# motor_control_cape.net
KiCad netlist of a schematic drawn in EAGLE
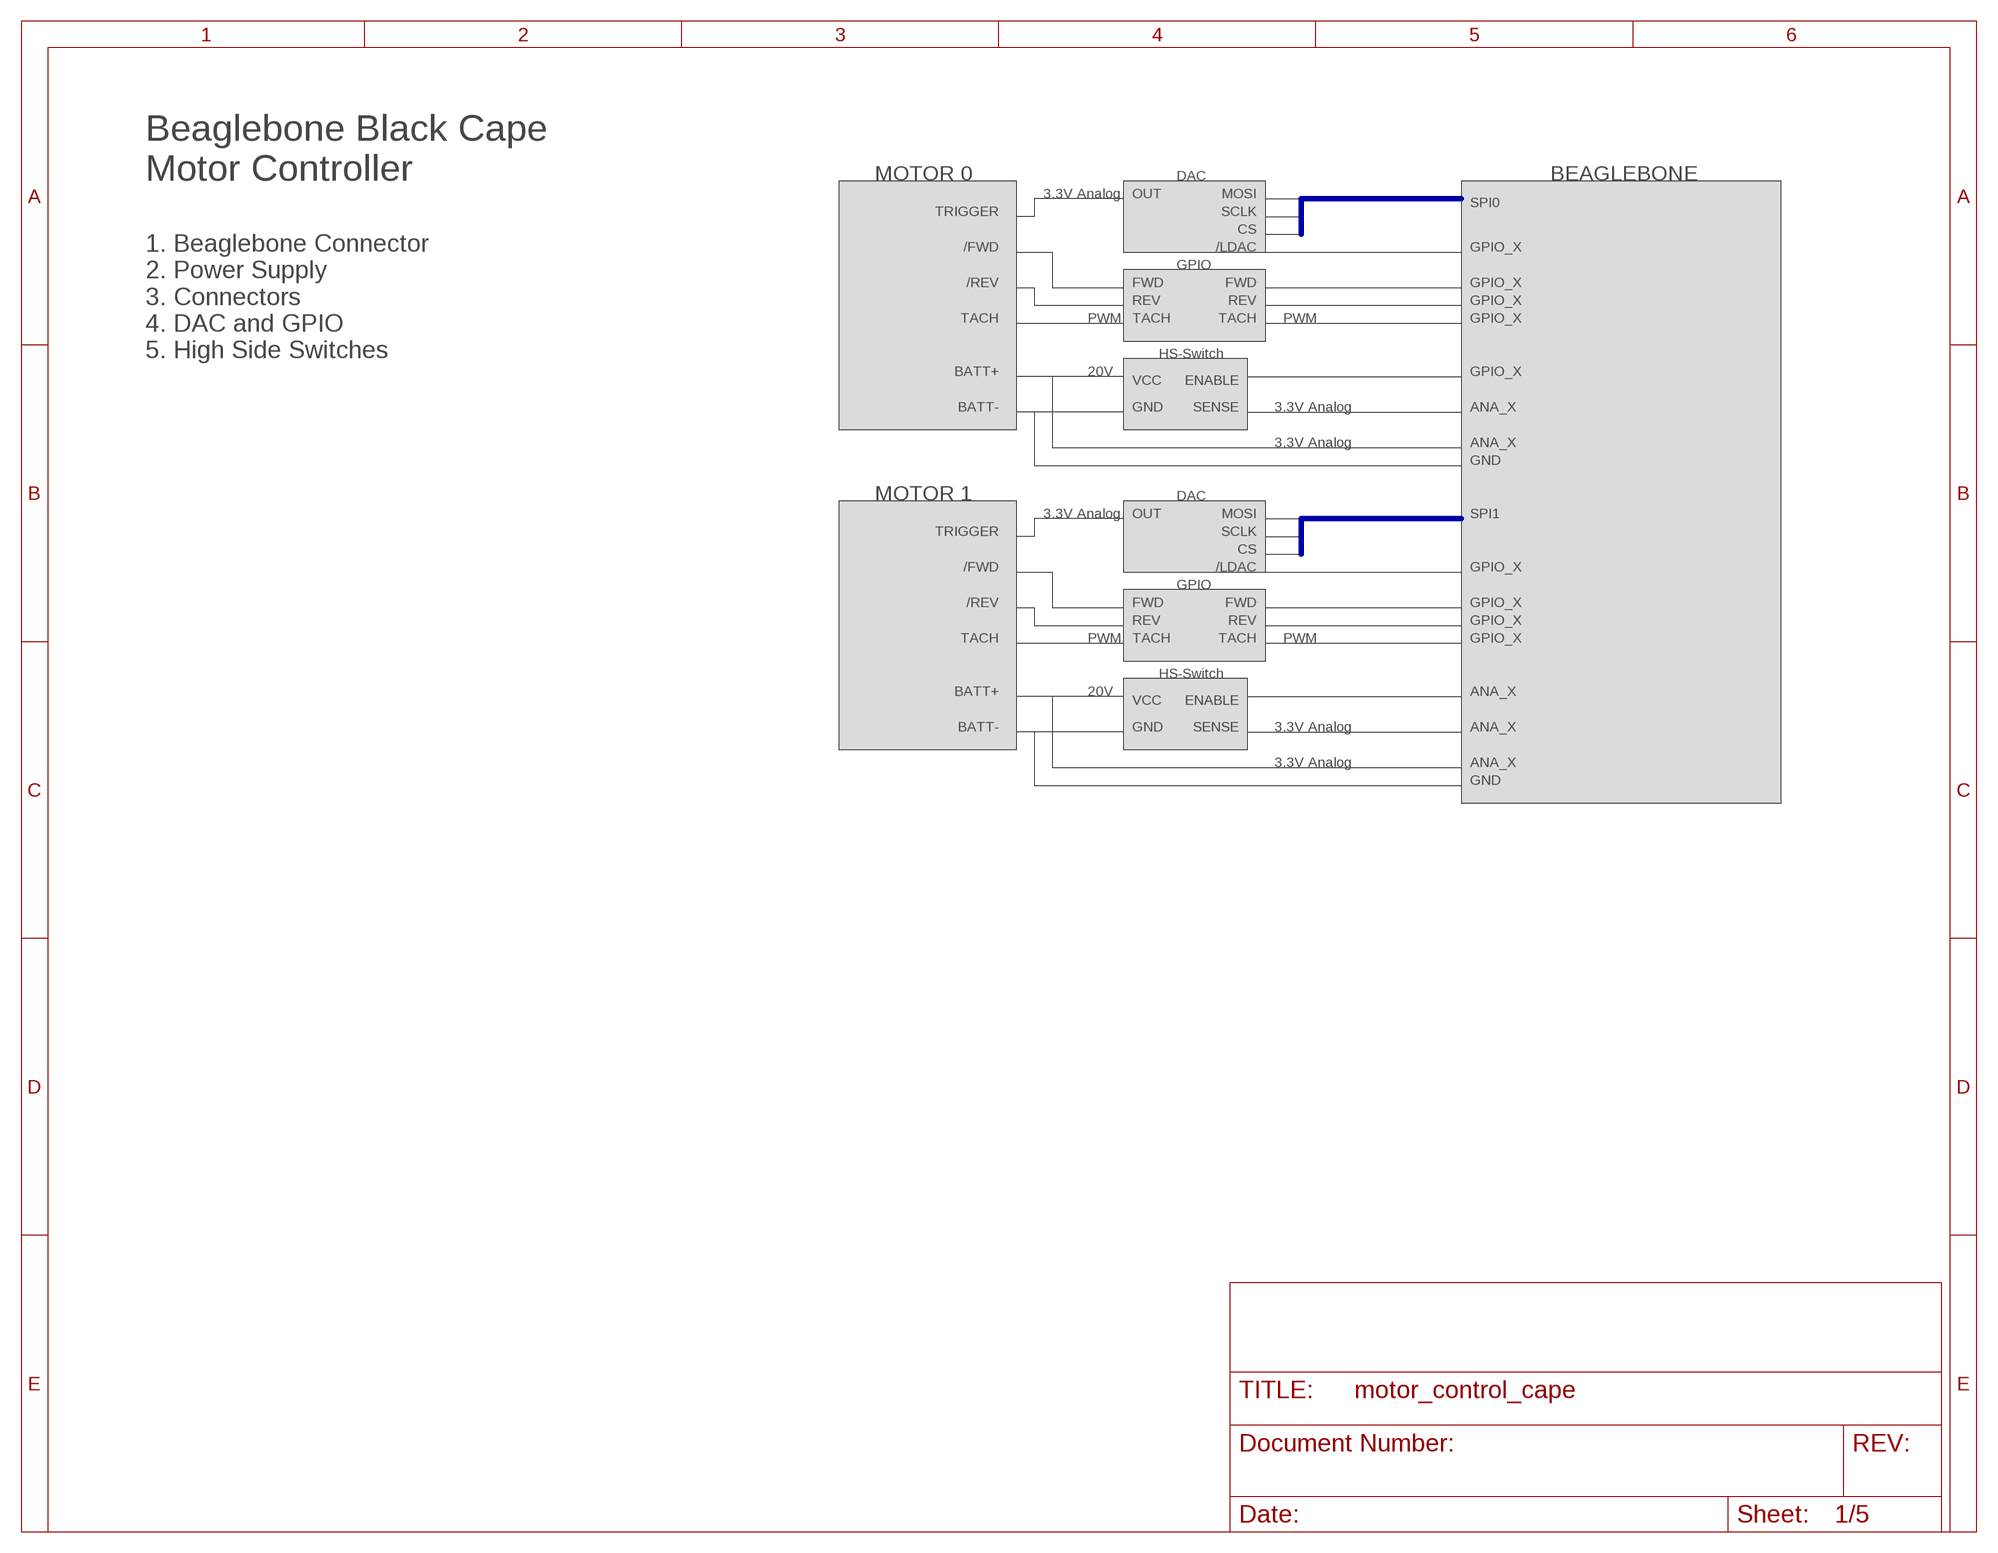
[diagram p0: schematic, sheet 1]
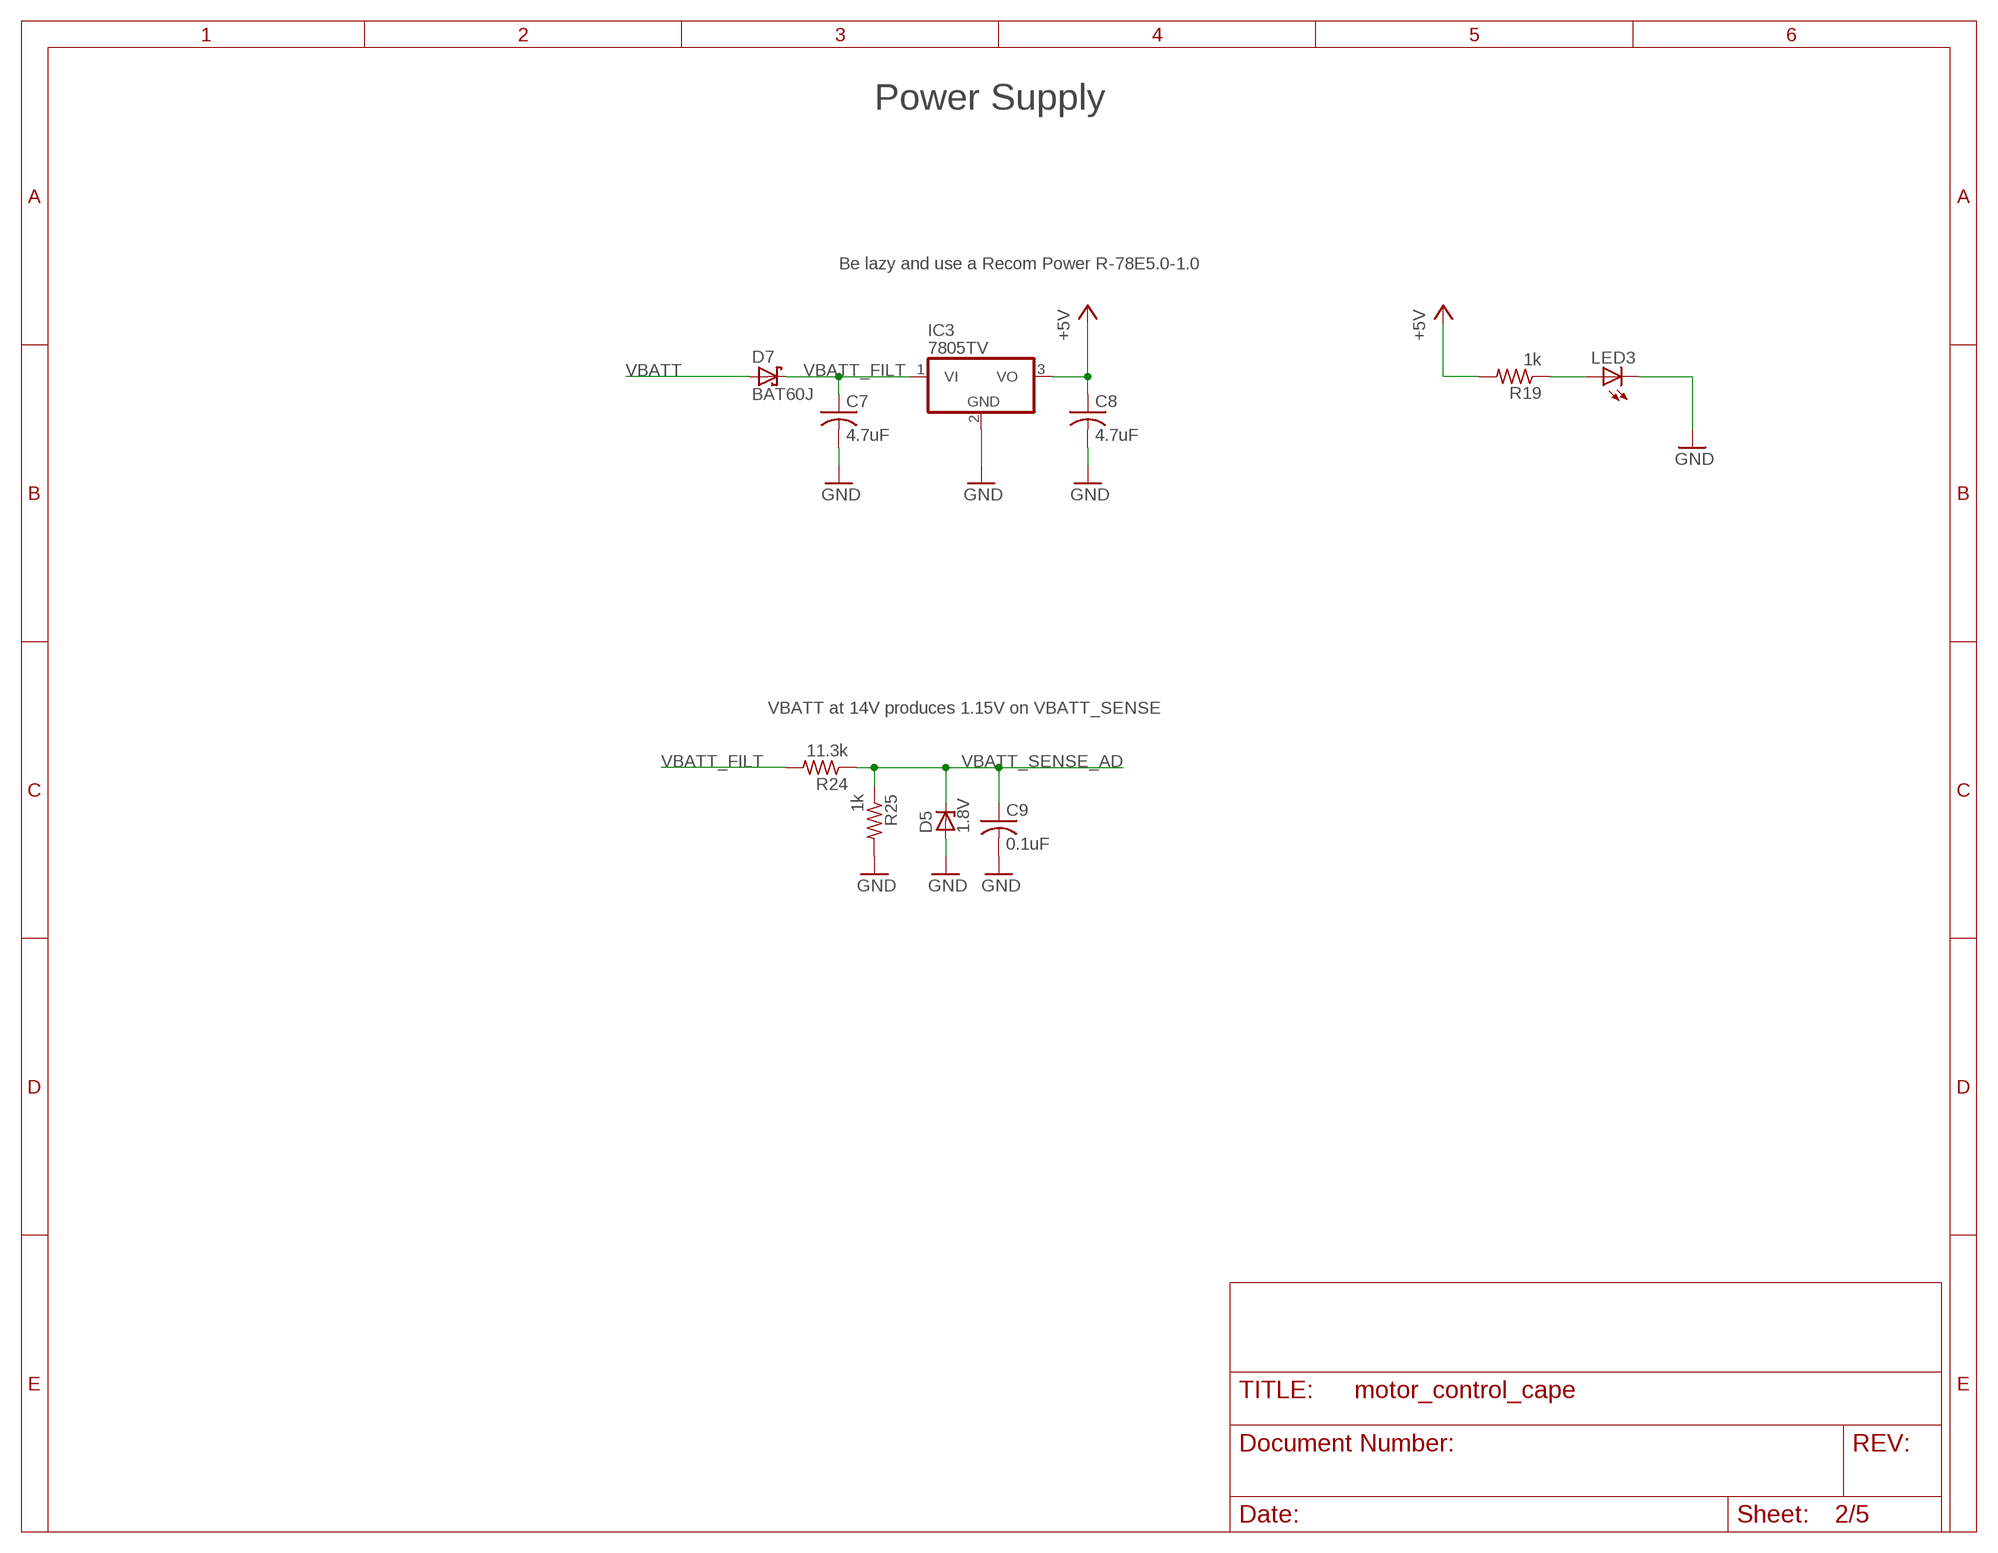
[diagram p1: schematic, sheet 2]
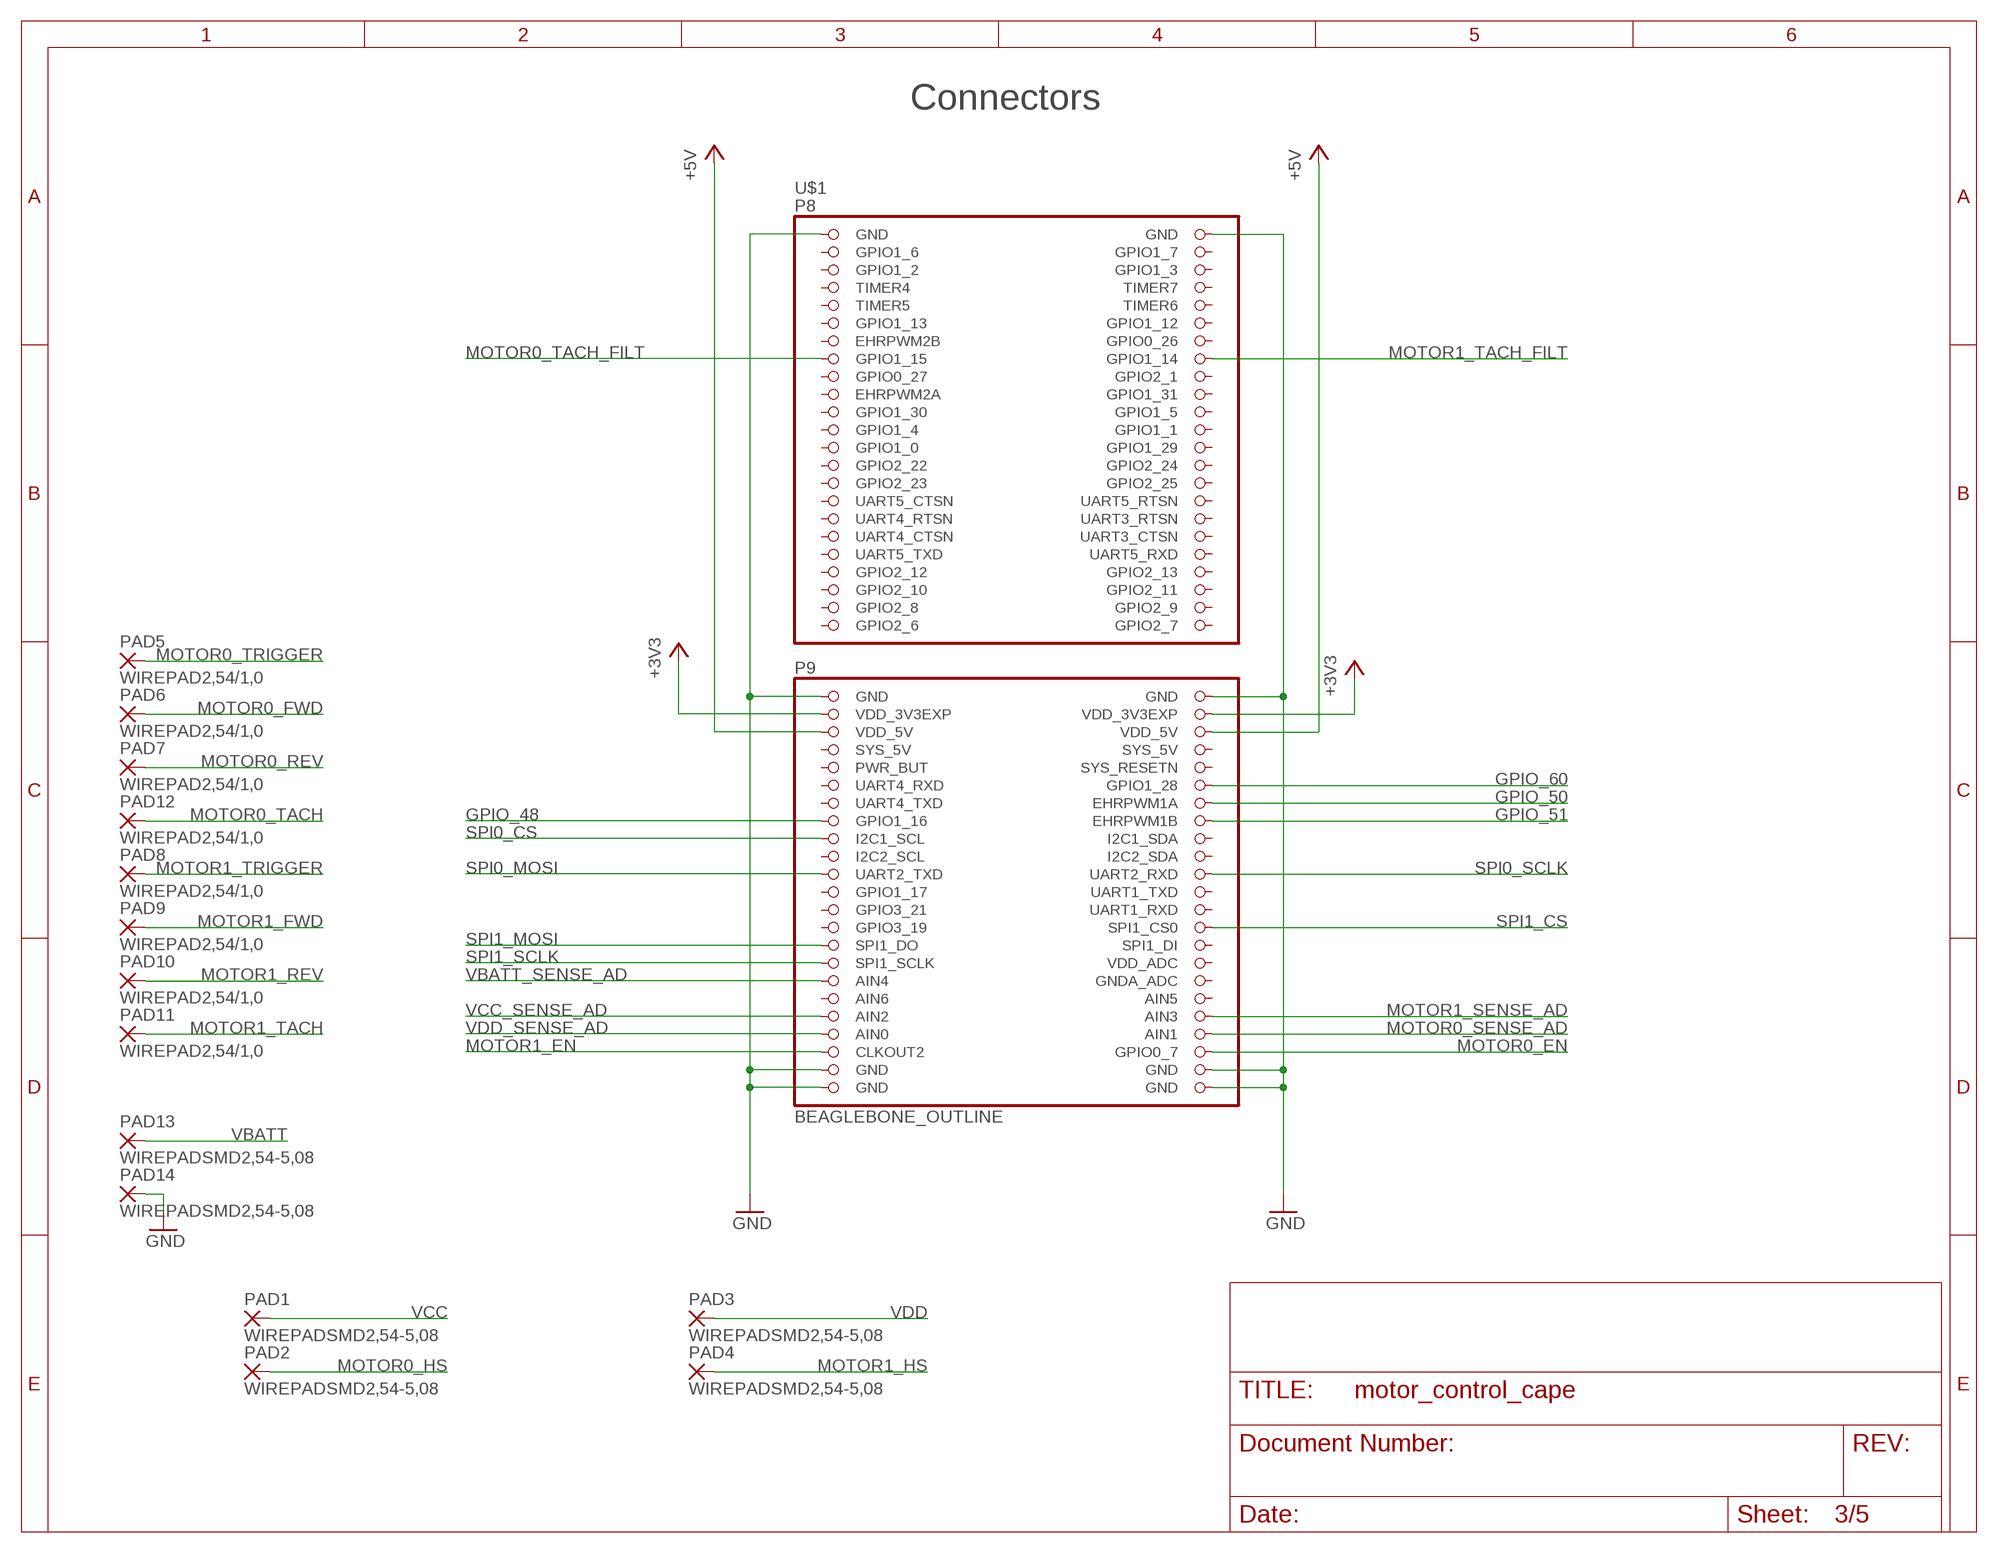
[diagram p2: schematic, sheet 3]
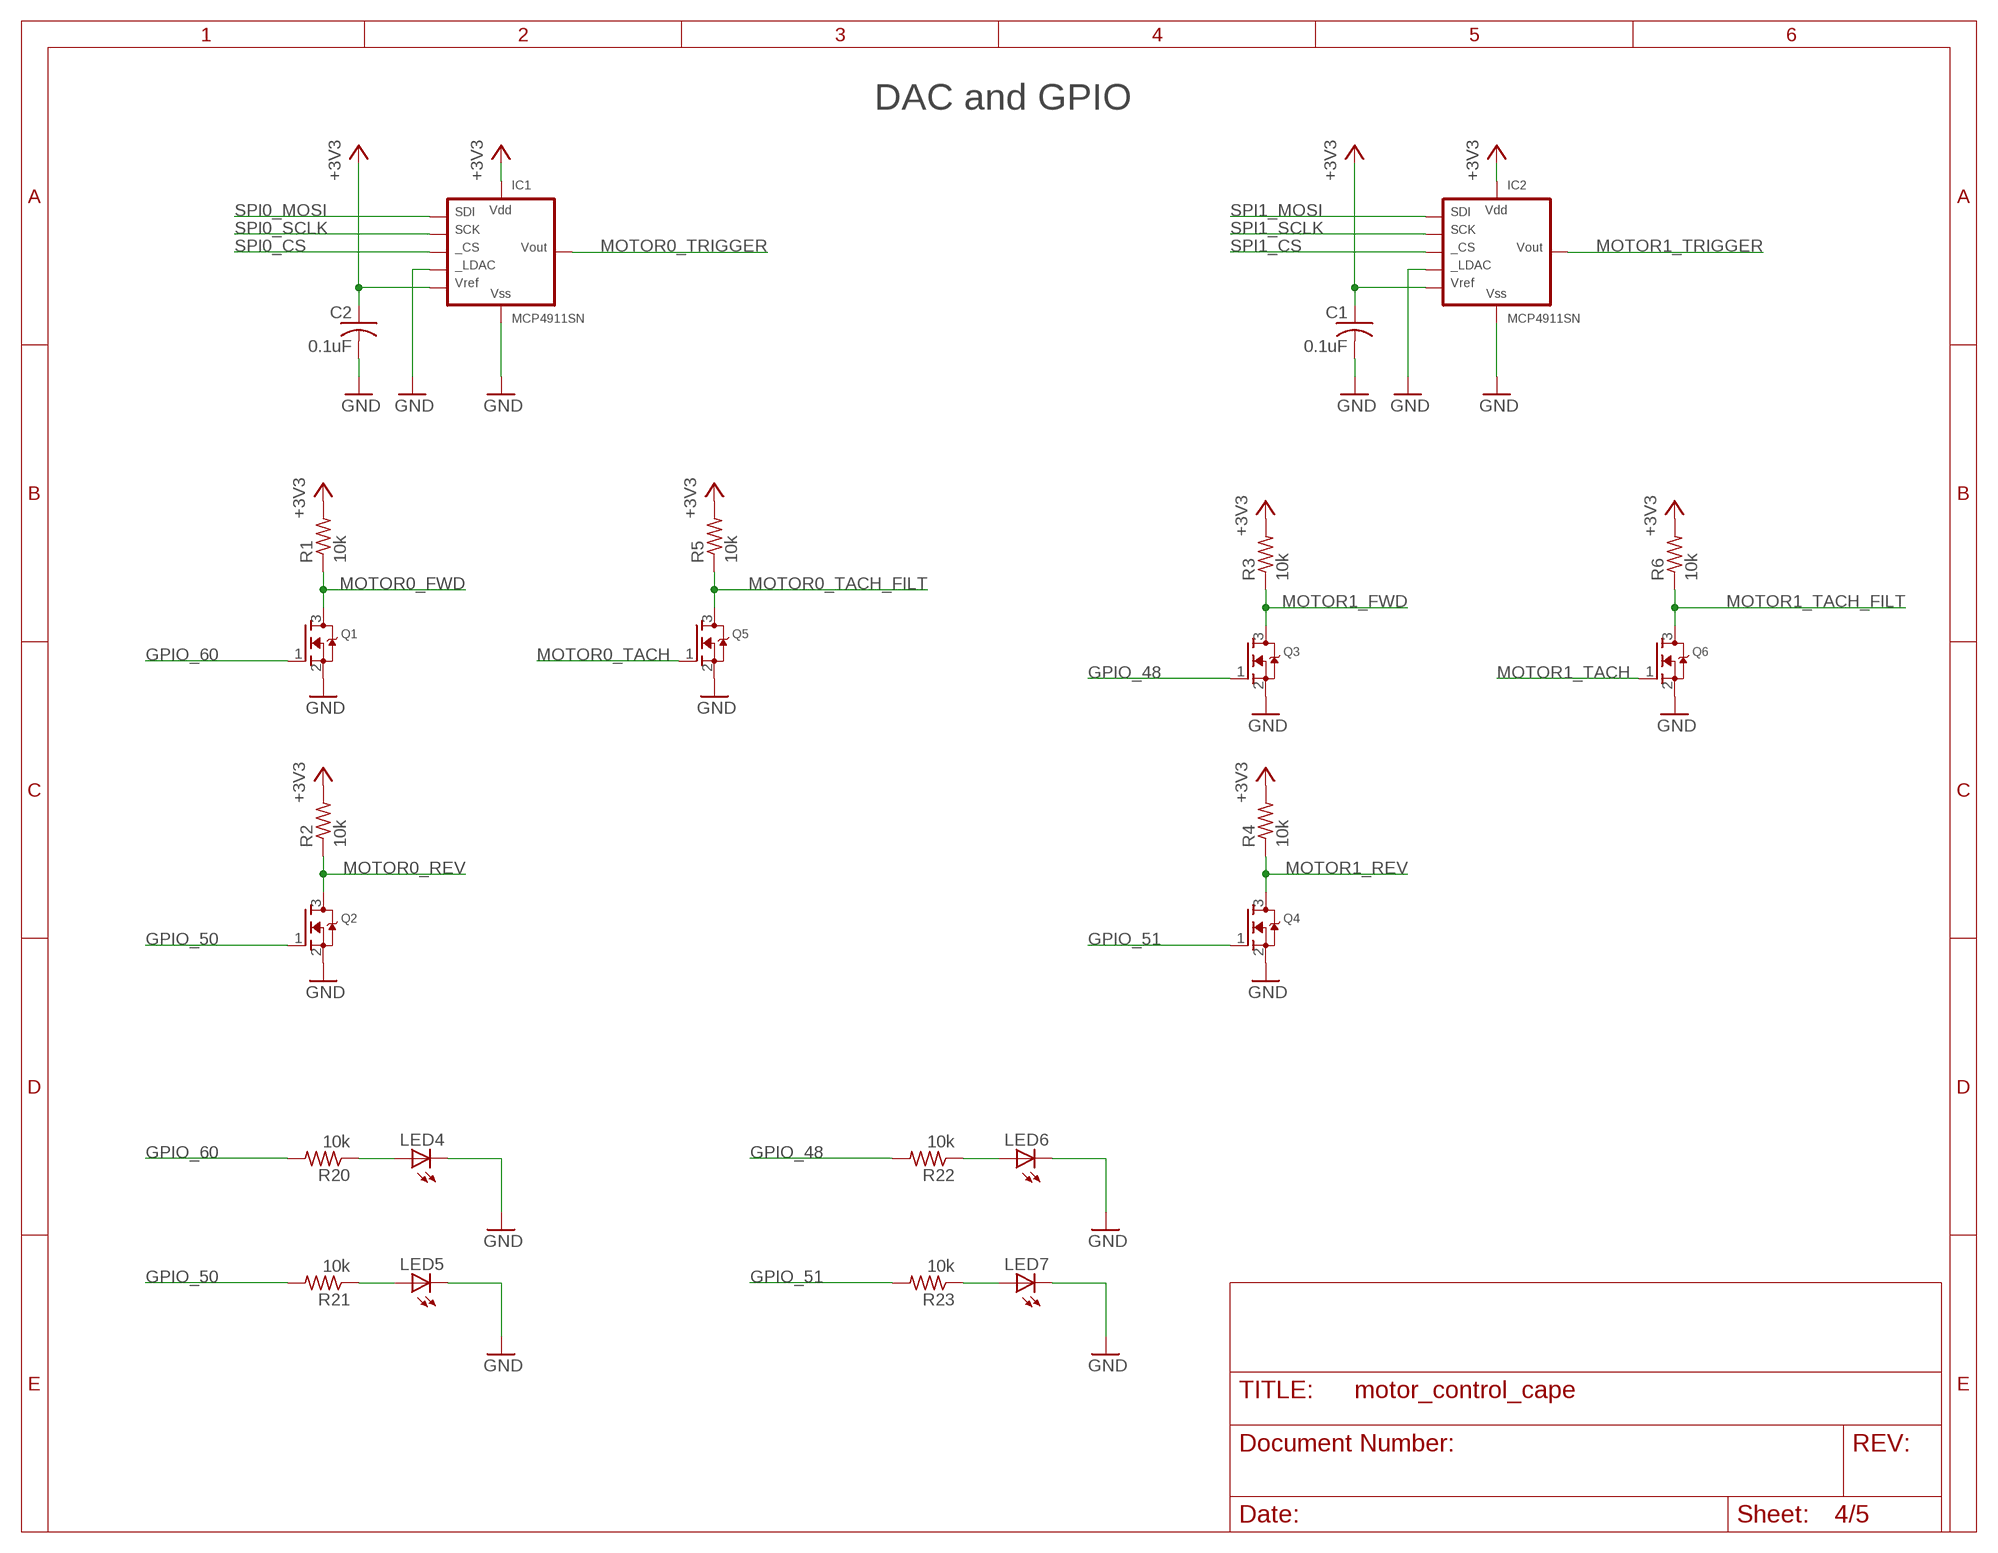
[diagram p3: schematic, sheet 4]
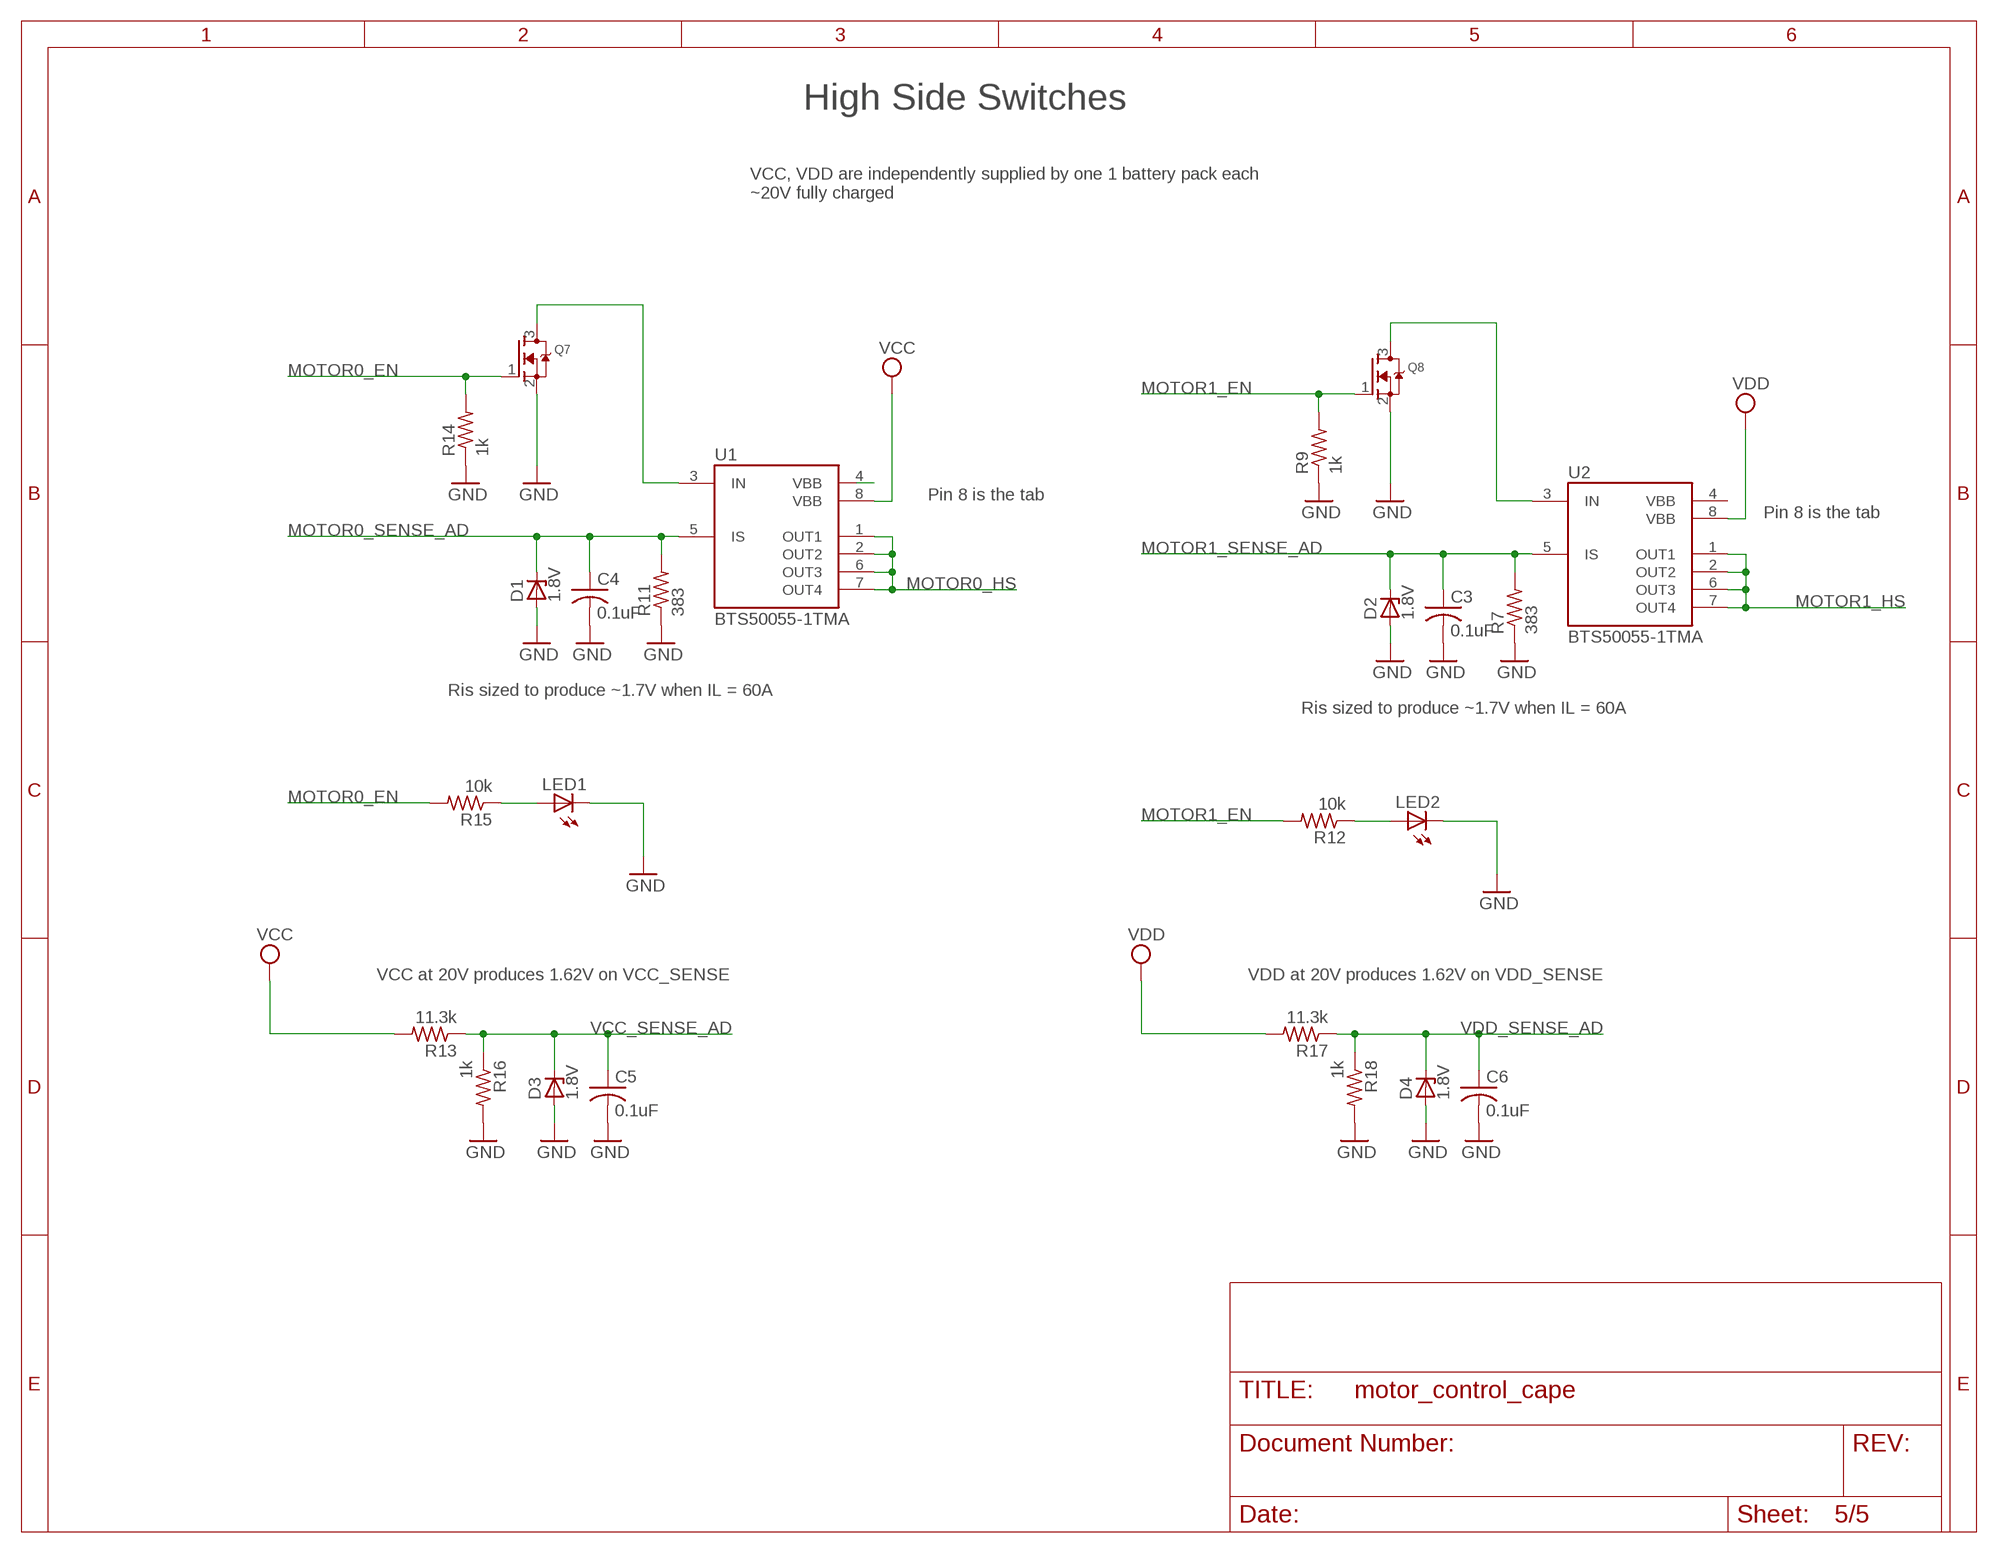
[diagram p4: schematic, sheet 5]

(export (version "E")
  (design (tool "Eeschema 10.0.6"))
  (components
    (comp (ref "C1")
      (value "0.1uF")
      (footprint "eagle-import:C0603")
      (libsource (lib "eagle-import") (part "C-USC0603"))
    )
    (comp (ref "C2")
      (value "0.1uF")
      (footprint "eagle-import:C0603")
      (libsource (lib "eagle-import") (part "C-USC0603"))
    )
    (comp (ref "IC1")
      (value "MCP4911SN")
      (footprint "eagle-import:SO-08")
      (libsource (lib "eagle-import") (part "MCP4911SN"))
    )
    (comp (ref "IC2")
      (value "MCP4911SN")
      (footprint "eagle-import:SO-08")
      (libsource (lib "eagle-import") (part "MCP4911SN"))
    )
    (comp (ref "LED4")
      (value "LEDCHIPLED_0603")
      (footprint "eagle-import:CHIPLED_0603")
      (libsource (lib "eagle-import") (part "LEDCHIPLED_0603"))
    )
    (comp (ref "LED5")
      (value "LEDCHIPLED_0603")
      (footprint "eagle-import:CHIPLED_0603")
      (libsource (lib "eagle-import") (part "LEDCHIPLED_0603"))
    )
    (comp (ref "LED6")
      (value "LEDCHIPLED_0603")
      (footprint "eagle-import:CHIPLED_0603")
      (libsource (lib "eagle-import") (part "LEDCHIPLED_0603"))
    )
    (comp (ref "LED7")
      (value "LEDCHIPLED_0603")
      (footprint "eagle-import:CHIPLED_0603")
      (libsource (lib "eagle-import") (part "LEDCHIPLED_0603"))
    )
    (comp (ref "Q1")
      (value "MOSFET-NREFLOW")
      (footprint "eagle-import:SOT23")
      (libsource (lib "eagle-import") (part "MOSFET-NREFLOW"))
    )
    (comp (ref "Q2")
      (value "MOSFET-NREFLOW")
      (footprint "eagle-import:SOT23")
      (libsource (lib "eagle-import") (part "MOSFET-NREFLOW"))
    )
    (comp (ref "Q3")
      (value "MOSFET-NREFLOW")
      (footprint "eagle-import:SOT23")
      (libsource (lib "eagle-import") (part "MOSFET-NREFLOW"))
    )
    (comp (ref "Q4")
      (value "MOSFET-NREFLOW")
      (footprint "eagle-import:SOT23")
      (libsource (lib "eagle-import") (part "MOSFET-NREFLOW"))
    )
    (comp (ref "Q5")
      (value "MOSFET-NREFLOW")
      (footprint "eagle-import:SOT23")
      (libsource (lib "eagle-import") (part "MOSFET-NREFLOW"))
    )
    (comp (ref "Q6")
      (value "MOSFET-NREFLOW")
      (footprint "eagle-import:SOT23")
      (libsource (lib "eagle-import") (part "MOSFET-NREFLOW"))
    )
    (comp (ref "R1")
      (value "10k")
      (footprint "eagle-import:R0603")
      (libsource (lib "eagle-import") (part "resistor_R-US_R0603"))
    )
    (comp (ref "R2")
      (value "10k")
      (footprint "eagle-import:R0603")
      (libsource (lib "eagle-import") (part "resistor_R-US_R0603"))
    )
    (comp (ref "R3")
      (value "10k")
      (footprint "eagle-import:R0603")
      (libsource (lib "eagle-import") (part "resistor_R-US_R0603"))
    )
    (comp (ref "R4")
      (value "10k")
      (footprint "eagle-import:R0603")
      (libsource (lib "eagle-import") (part "resistor_R-US_R0603"))
    )
    (comp (ref "R5")
      (value "10k")
      (footprint "eagle-import:R0603")
      (libsource (lib "eagle-import") (part "resistor_R-US_R0603"))
    )
    (comp (ref "R6")
      (value "10k")
      (footprint "eagle-import:R0603")
      (libsource (lib "eagle-import") (part "resistor_R-US_R0603"))
    )
    (comp (ref "R20")
      (value "10k")
      (footprint "eagle-import:R0603")
      (libsource (lib "eagle-import") (part "R-US_R0603"))
    )
    (comp (ref "R21")
      (value "10k")
      (footprint "eagle-import:R0603")
      (libsource (lib "eagle-import") (part "R-US_R0603"))
    )
    (comp (ref "R22")
      (value "10k")
      (footprint "eagle-import:R0603")
      (libsource (lib "eagle-import") (part "R-US_R0603"))
    )
    (comp (ref "R23")
      (value "10k")
      (footprint "eagle-import:R0603")
      (libsource (lib "eagle-import") (part "R-US_R0603"))
    )
    (comp (ref "C3")
      (value "0.1uF")
      (footprint "eagle-import:C0603")
      (libsource (lib "eagle-import") (part "C-USC0603"))
    )
    (comp (ref "C4")
      (value "0.1uF")
      (footprint "eagle-import:C0603")
      (libsource (lib "eagle-import") (part "C-USC0603"))
    )
    (comp (ref "C5")
      (value "0.1uF")
      (footprint "eagle-import:C0603")
      (libsource (lib "eagle-import") (part "C-USC0603"))
    )
    (comp (ref "C6")
      (value "0.1uF")
      (footprint "eagle-import:C0603")
      (libsource (lib "eagle-import") (part "C-USC0603"))
    )
    (comp (ref "D1")
      (value "1.8V")
      (footprint "eagle-import:SOT23")
      (libsource (lib "eagle-import") (part "ZENER-DIODESOT23"))
    )
    (comp (ref "D2")
      (value "1.8V")
      (footprint "eagle-import:SOT23")
      (libsource (lib "eagle-import") (part "ZENER-DIODESOT23"))
    )
    (comp (ref "D3")
      (value "1.8V")
      (footprint "eagle-import:SOT23")
      (libsource (lib "eagle-import") (part "ZENER-DIODESOT23"))
    )
    (comp (ref "D4")
      (value "1.8V")
      (footprint "eagle-import:SOT23")
      (libsource (lib "eagle-import") (part "ZENER-DIODESOT23"))
    )
    (comp (ref "LED1")
      (value "LEDCHIPLED_0603")
      (footprint "eagle-import:CHIPLED_0603")
      (libsource (lib "eagle-import") (part "LEDCHIPLED_0603"))
    )
    (comp (ref "LED2")
      (value "LEDCHIPLED_0603")
      (footprint "eagle-import:CHIPLED_0603")
      (libsource (lib "eagle-import") (part "LEDCHIPLED_0603"))
    )
    (comp (ref "Q7")
      (value "MOSFET-NREFLOW")
      (footprint "eagle-import:SOT23")
      (libsource (lib "eagle-import") (part "MOSFET-NREFLOW"))
    )
    (comp (ref "Q8")
      (value "MOSFET-NREFLOW")
      (footprint "eagle-import:SOT23")
      (libsource (lib "eagle-import") (part "MOSFET-NREFLOW"))
    )
    (comp (ref "R7")
      (value "383")
      (footprint "eagle-import:R0603")
      (libsource (lib "eagle-import") (part "R-US_R0603"))
    )
    (comp (ref "R9")
      (value "1k")
      (footprint "eagle-import:R0603")
      (libsource (lib "eagle-import") (part "R-US_R0603"))
    )
    (comp (ref "R11")
      (value "383")
      (footprint "eagle-import:R0603")
      (libsource (lib "eagle-import") (part "R-US_R0603"))
    )
    (comp (ref "R12")
      (value "10k")
      (footprint "eagle-import:R0603")
      (libsource (lib "eagle-import") (part "R-US_R0603"))
    )
    (comp (ref "R13")
      (value "11.3k")
      (footprint "eagle-import:R0603")
      (libsource (lib "eagle-import") (part "R-US_R0603"))
    )
    (comp (ref "R14")
      (value "1k")
      (footprint "eagle-import:R0603")
      (libsource (lib "eagle-import") (part "R-US_R0603"))
    )
    (comp (ref "R15")
      (value "10k")
      (footprint "eagle-import:R0603")
      (libsource (lib "eagle-import") (part "R-US_R0603"))
    )
    (comp (ref "R16")
      (value "1k")
      (footprint "eagle-import:R0603")
      (libsource (lib "eagle-import") (part "R-US_R0603"))
    )
    (comp (ref "R17")
      (value "11.3k")
      (footprint "eagle-import:R0603")
      (libsource (lib "eagle-import") (part "R-US_R0603"))
    )
    (comp (ref "R18")
      (value "1k")
      (footprint "eagle-import:R0603")
      (libsource (lib "eagle-import") (part "R-US_R0603"))
    )
    (comp (ref "U1")
      (value "BTS50055-1TMA")
      (footprint "eagle-import:TO127P1385X450-8N-V")
      (libsource (lib "eagle-import") (part "BTS50055-1TMA"))
    )
    (comp (ref "U2")
      (value "BTS50055-1TMA")
      (footprint "eagle-import:TO127P1385X450-8N-V")
      (libsource (lib "eagle-import") (part "BTS50055-1TMA"))
    )
    (comp (ref "PAD1")
      (value "WIREPADSMD2,54-5,08")
      (footprint "eagle-import:SMD2,54-5,08")
      (libsource (lib "eagle-import") (part "WIREPADSMD2,54-5,08"))
    )
    (comp (ref "PAD2")
      (value "WIREPADSMD2,54-5,08")
      (footprint "eagle-import:SMD2,54-5,08")
      (libsource (lib "eagle-import") (part "WIREPADSMD2,54-5,08"))
    )
    (comp (ref "PAD3")
      (value "WIREPADSMD2,54-5,08")
      (footprint "eagle-import:SMD2,54-5,08")
      (libsource (lib "eagle-import") (part "WIREPADSMD2,54-5,08"))
    )
    (comp (ref "PAD4")
      (value "WIREPADSMD2,54-5,08")
      (footprint "eagle-import:SMD2,54-5,08")
      (libsource (lib "eagle-import") (part "WIREPADSMD2,54-5,08"))
    )
    (comp (ref "PAD5")
      (value "WIREPAD2,54/1,0")
      (footprint "eagle-import:2,54_1,0")
      (libsource (lib "eagle-import") (part "WIREPAD2,54/1,0"))
    )
    (comp (ref "PAD6")
      (value "WIREPAD2,54/1,0")
      (footprint "eagle-import:2,54_1,0")
      (libsource (lib "eagle-import") (part "WIREPAD2,54/1,0"))
    )
    (comp (ref "PAD7")
      (value "WIREPAD2,54/1,0")
      (footprint "eagle-import:2,54_1,0")
      (libsource (lib "eagle-import") (part "WIREPAD2,54/1,0"))
    )
    (comp (ref "PAD8")
      (value "WIREPAD2,54/1,0")
      (footprint "eagle-import:2,54_1,0")
      (libsource (lib "eagle-import") (part "WIREPAD2,54/1,0"))
    )
    (comp (ref "PAD9")
      (value "WIREPAD2,54/1,0")
      (footprint "eagle-import:2,54_1,0")
      (libsource (lib "eagle-import") (part "WIREPAD2,54/1,0"))
    )
    (comp (ref "PAD10")
      (value "WIREPAD2,54/1,0")
      (footprint "eagle-import:2,54_1,0")
      (libsource (lib "eagle-import") (part "WIREPAD2,54/1,0"))
    )
    (comp (ref "PAD11")
      (value "WIREPAD2,54/1,0")
      (footprint "eagle-import:2,54_1,0")
      (libsource (lib "eagle-import") (part "WIREPAD2,54/1,0"))
    )
    (comp (ref "PAD12")
      (value "WIREPAD2,54/1,0")
      (footprint "eagle-import:2,54_1,0")
      (libsource (lib "eagle-import") (part "WIREPAD2,54/1,0"))
    )
    (comp (ref "PAD13")
      (value "WIREPADSMD2,54-5,08")
      (footprint "eagle-import:SMD2,54-5,08")
      (libsource (lib "eagle-import") (part "WIREPADSMD2,54-5,08"))
    )
    (comp (ref "PAD14")
      (value "WIREPADSMD2,54-5,08")
      (footprint "eagle-import:SMD2,54-5,08")
      (libsource (lib "eagle-import") (part "WIREPADSMD2,54-5,08"))
    )
    (comp (ref "U$1")
      (value "BEAGLEBONE_OUTLINE")
      (footprint "eagle-import:BEAGLEBONE_SHIELD")
      (libsource (lib "eagle-import") (part "BEAGLEBONE_OUTLINE"))
    )
    (comp (ref "C7")
      (value "4.7uF")
      (footprint "eagle-import:C0805")
      (libsource (lib "eagle-import") (part "C-USC0805"))
    )
    (comp (ref "C8")
      (value "4.7uF")
      (footprint "eagle-import:C0805")
      (libsource (lib "eagle-import") (part "C-USC0805"))
    )
    (comp (ref "C9")
      (value "0.1uF")
      (footprint "eagle-import:C0603")
      (libsource (lib "eagle-import") (part "C-USC0603"))
    )
    (comp (ref "D5")
      (value "1.8V")
      (footprint "eagle-import:SOT23")
      (libsource (lib "eagle-import") (part "ZENER-DIODESOT23"))
    )
    (comp (ref "D7")
      (value "BAT60J")
      (footprint "eagle-import:SOD323_ST")
      (libsource (lib "eagle-import") (part "BAT60J"))
    )
    (comp (ref "IC3")
      (value "7805TV")
      (footprint "eagle-import:TO220V")
      (libsource (lib "eagle-import") (part "78TV05"))
    )
    (comp (ref "LED3")
      (value "LEDCHIPLED_0603")
      (footprint "eagle-import:CHIPLED_0603")
      (libsource (lib "eagle-import") (part "LEDCHIPLED_0603"))
    )
    (comp (ref "R19")
      (value "1k")
      (footprint "eagle-import:R0603")
      (libsource (lib "eagle-import") (part "R-US_R0603"))
    )
    (comp (ref "R24")
      (value "11.3k")
      (footprint "eagle-import:R0603")
      (libsource (lib "eagle-import") (part "R-US_R0603"))
    )
    (comp (ref "R25")
      (value "1k")
      (footprint "eagle-import:R0603")
      (libsource (lib "eagle-import") (part "R-US_R0603"))
    )
  )
  (nets
    (net (code "2") (name "+3V3") (class "Default")
      (node (ref "C1") (pin "1") (pinfunction "1_1") (pintype "passive"))
      (node (ref "C2") (pin "1") (pinfunction "1_1") (pintype "passive"))
      (node (ref "IC1") (pin "1") (pinfunction "VDD_1") (pintype "power_in"))
      (node (ref "IC1") (pin "6") (pinfunction "VREF_6") (pintype "input"))
      (node (ref "IC2") (pin "1") (pinfunction "VDD_1") (pintype "power_in"))
      (node (ref "IC2") (pin "6") (pinfunction "VREF_6") (pintype "input"))
      (node (ref "R1") (pin "2") (pinfunction "2_2") (pintype "passive"))
      (node (ref "R2") (pin "2") (pinfunction "2_2") (pintype "passive"))
      (node (ref "R3") (pin "2") (pinfunction "2_2") (pintype "passive"))
      (node (ref "R4") (pin "2") (pinfunction "2_2") (pintype "passive"))
      (node (ref "R5") (pin "2") (pinfunction "2_2") (pintype "passive"))
      (node (ref "R6") (pin "2") (pinfunction "2_2") (pintype "passive"))
      (node (ref "U$1") (pin "49") (pinfunction "VDD_3V3EXP_49") (pintype "power_in"))
      (node (ref "U$1") (pin "50") (pinfunction "VDD_3V3EXP_50") (pintype "power_in"))
    )
    (net (code "3") (name "+5V") (class "Default")
      (node (ref "C8") (pin "1") (pinfunction "1_1") (pintype "passive"))
      (node (ref "IC3") (pin "3") (pinfunction "VO_3") (pintype "passive"))
      (node (ref "R19") (pin "2") (pinfunction "2_2") (pintype "passive"))
      (node (ref "U$1") (pin "51") (pinfunction "VDD_5V_51") (pintype "power_in"))
      (node (ref "U$1") (pin "52") (pinfunction "VDD_5V_52") (pintype "power_in"))
    )
    (net (code "5") (name "GND") (class "Default")
      (node (ref "C1") (pin "2") (pinfunction "2_2") (pintype "passive"))
      (node (ref "C2") (pin "2") (pinfunction "2_2") (pintype "passive"))
      (node (ref "C3") (pin "2") (pinfunction "2_2") (pintype "passive"))
      (node (ref "C4") (pin "2") (pinfunction "2_2") (pintype "passive"))
      (node (ref "C5") (pin "2") (pinfunction "2_2") (pintype "passive"))
      (node (ref "C6") (pin "2") (pinfunction "2_2") (pintype "passive"))
      (node (ref "C7") (pin "2") (pinfunction "2_2") (pintype "passive"))
      (node (ref "C8") (pin "2") (pinfunction "2_2") (pintype "passive"))
      (node (ref "C9") (pin "2") (pinfunction "2_2") (pintype "passive"))
      (node (ref "D1") (pin "1") (pinfunction "A_1") (pintype "passive"))
      (node (ref "D2") (pin "1") (pinfunction "A_1") (pintype "passive"))
      (node (ref "D3") (pin "1") (pinfunction "A_1") (pintype "passive"))
      (node (ref "D4") (pin "1") (pinfunction "A_1") (pintype "passive"))
      (node (ref "D5") (pin "1") (pinfunction "A_1") (pintype "passive"))
      (node (ref "IC1") (pin "5") (pinfunction "LDAC_5") (pintype "input"))
      (node (ref "IC1") (pin "7") (pinfunction "VSS_7") (pintype "power_in"))
      (node (ref "IC2") (pin "5") (pinfunction "LDAC_5") (pintype "input"))
      (node (ref "IC2") (pin "7") (pinfunction "VSS_7") (pintype "power_in"))
      (node (ref "IC3") (pin "2") (pinfunction "GND_2") (pintype "passive"))
      (node (ref "LED1") (pin "C") (pinfunction "C_C") (pintype "passive"))
      (node (ref "LED2") (pin "C") (pinfunction "C_C") (pintype "passive"))
      (node (ref "LED3") (pin "C") (pinfunction "C_C") (pintype "passive"))
      (node (ref "LED4") (pin "C") (pinfunction "C_C") (pintype "passive"))
      (node (ref "LED5") (pin "C") (pinfunction "C_C") (pintype "passive"))
      (node (ref "LED6") (pin "C") (pinfunction "C_C") (pintype "passive"))
      (node (ref "LED7") (pin "C") (pinfunction "C_C") (pintype "passive"))
      (node (ref "PAD14") (pin "1") (pinfunction "P_1") (pintype "passive"))
      (node (ref "Q1") (pin "2") (pinfunction "S_2") (pintype "bidirectional"))
      (node (ref "Q2") (pin "2") (pinfunction "S_2") (pintype "bidirectional"))
      (node (ref "Q3") (pin "2") (pinfunction "S_2") (pintype "bidirectional"))
      (node (ref "Q4") (pin "2") (pinfunction "S_2") (pintype "bidirectional"))
      (node (ref "Q5") (pin "2") (pinfunction "S_2") (pintype "bidirectional"))
      (node (ref "Q6") (pin "2") (pinfunction "S_2") (pintype "bidirectional"))
      (node (ref "Q7") (pin "2") (pinfunction "S_2") (pintype "bidirectional"))
      (node (ref "Q8") (pin "2") (pinfunction "S_2") (pintype "bidirectional"))
      (node (ref "R11") (pin "1") (pinfunction "1_1") (pintype "passive"))
      (node (ref "R14") (pin "1") (pinfunction "1_1") (pintype "passive"))
      (node (ref "R16") (pin "2") (pinfunction "2_2") (pintype "passive"))
      (node (ref "R18") (pin "2") (pinfunction "2_2") (pintype "passive"))
      (node (ref "R25") (pin "2") (pinfunction "2_2") (pintype "passive"))
      (node (ref "R7") (pin "1") (pinfunction "1_1") (pintype "passive"))
      (node (ref "R9") (pin "1") (pinfunction "1_1") (pintype "passive"))
      (node (ref "U$1") (pin "1") (pinfunction "GND_1") (pintype "power_in"))
      (node (ref "U$1") (pin "2") (pinfunction "GND_2") (pintype "power_in"))
      (node (ref "U$1") (pin "47") (pinfunction "GND_47") (pintype "power_in"))
      (node (ref "U$1") (pin "48") (pinfunction "GND_48") (pintype "power_in"))
      (node (ref "U$1") (pin "89") (pinfunction "GND_89") (pintype "power_in"))
      (node (ref "U$1") (pin "90") (pinfunction "GND_90") (pintype "power_in"))
      (node (ref "U$1") (pin "91") (pinfunction "GND_91") (pintype "power_in"))
      (node (ref "U$1") (pin "92") (pinfunction "GND_92") (pintype "power_in"))
    )
    (net (code "6") (name "GPIO_48") (class "Default")
      (node (ref "Q3") (pin "1") (pinfunction "G_1") (pintype "bidirectional"))
      (node (ref "R22") (pin "2") (pinfunction "2_2") (pintype "passive"))
      (node (ref "U$1") (pin "61") (pinfunction "GPIO1_16_61") (pintype "passive"))
    )
    (net (code "7") (name "GPIO_50") (class "Default")
      (node (ref "Q2") (pin "1") (pinfunction "G_1") (pintype "bidirectional"))
      (node (ref "R21") (pin "2") (pinfunction "2_2") (pintype "passive"))
      (node (ref "U$1") (pin "60") (pinfunction "EHRPWM1A_60") (pintype "passive"))
    )
    (net (code "8") (name "GPIO_51") (class "Default")
      (node (ref "Q4") (pin "1") (pinfunction "G_1") (pintype "bidirectional"))
      (node (ref "R23") (pin "2") (pinfunction "2_2") (pintype "passive"))
      (node (ref "U$1") (pin "62") (pinfunction "EHRPWM1B_62") (pintype "passive"))
    )
    (net (code "9") (name "GPIO_60") (class "Default")
      (node (ref "Q1") (pin "1") (pinfunction "G_1") (pintype "bidirectional"))
      (node (ref "R20") (pin "2") (pinfunction "2_2") (pintype "passive"))
      (node (ref "U$1") (pin "58") (pinfunction "GPIO1_28_58") (pintype "passive"))
    )
    (net (code "10") (name "MOTOR0_EN") (class "Default")
      (node (ref "Q7") (pin "1") (pinfunction "G_1") (pintype "bidirectional"))
      (node (ref "R14") (pin "2") (pinfunction "2_2") (pintype "passive"))
      (node (ref "R15") (pin "2") (pinfunction "2_2") (pintype "passive"))
      (node (ref "U$1") (pin "88") (pinfunction "GPIO0_7_88") (pintype "passive"))
    )
    (net (code "11") (name "MOTOR0_FWD") (class "Default")
      (node (ref "PAD6") (pin "1") (pinfunction "P_1") (pintype "passive"))
      (node (ref "Q1") (pin "3") (pinfunction "D_3") (pintype "bidirectional"))
      (node (ref "R1") (pin "1") (pinfunction "1_1") (pintype "passive"))
    )
    (net (code "12") (name "MOTOR0_HS") (class "Default")
      (node (ref "PAD2") (pin "1") (pinfunction "P_1") (pintype "passive"))
      (node (ref "U1") (pin "1") (pinfunction "OUT1_1") (pintype "output"))
      (node (ref "U1") (pin "2") (pinfunction "OUT2_2") (pintype "output"))
      (node (ref "U1") (pin "6") (pinfunction "OUT3_6") (pintype "output"))
      (node (ref "U1") (pin "7") (pinfunction "OUT4_7") (pintype "output"))
    )
    (net (code "13") (name "MOTOR0_REV") (class "Default")
      (node (ref "PAD7") (pin "1") (pinfunction "P_1") (pintype "passive"))
      (node (ref "Q2") (pin "3") (pinfunction "D_3") (pintype "bidirectional"))
      (node (ref "R2") (pin "1") (pinfunction "1_1") (pintype "passive"))
    )
    (net (code "14") (name "MOTOR0_SENSE_AD") (class "Default")
      (node (ref "C4") (pin "1") (pinfunction "1_1") (pintype "passive"))
      (node (ref "D1") (pin "3") (pinfunction "C_3") (pintype "passive"))
      (node (ref "R11") (pin "2") (pinfunction "2_2") (pintype "passive"))
      (node (ref "U$1") (pin "86") (pinfunction "AIN1_86") (pintype "passive"))
      (node (ref "U1") (pin "5") (pinfunction "IS_5") (pintype "output"))
    )
    (net (code "15") (name "MOTOR0_TACH") (class "Default")
      (node (ref "PAD12") (pin "1") (pinfunction "P_1") (pintype "passive"))
      (node (ref "Q5") (pin "1") (pinfunction "G_1") (pintype "bidirectional"))
    )
    (net (code "16") (name "MOTOR0_TACH_FILT") (class "Default")
      (node (ref "Q5") (pin "3") (pinfunction "D_3") (pintype "bidirectional"))
      (node (ref "R5") (pin "1") (pinfunction "1_1") (pintype "passive"))
      (node (ref "U$1") (pin "15") (pinfunction "GPIO1_15_15") (pintype "passive"))
    )
    (net (code "17") (name "MOTOR0_TRIGGER") (class "Default")
      (node (ref "IC1") (pin "8") (pinfunction "VOUT_8") (pintype "output"))
      (node (ref "PAD5") (pin "1") (pinfunction "P_1") (pintype "passive"))
    )
    (net (code "18") (name "MOTOR1_EN") (class "Default")
      (node (ref "Q8") (pin "1") (pinfunction "G_1") (pintype "bidirectional"))
      (node (ref "R12") (pin "2") (pinfunction "2_2") (pintype "passive"))
      (node (ref "R9") (pin "2") (pinfunction "2_2") (pintype "passive"))
      (node (ref "U$1") (pin "87") (pinfunction "CLKOUT2_87") (pintype "input"))
    )
    (net (code "19") (name "MOTOR1_FWD") (class "Default")
      (node (ref "PAD9") (pin "1") (pinfunction "P_1") (pintype "passive"))
      (node (ref "Q3") (pin "3") (pinfunction "D_3") (pintype "bidirectional"))
      (node (ref "R3") (pin "1") (pinfunction "1_1") (pintype "passive"))
    )
    (net (code "20") (name "MOTOR1_HS") (class "Default")
      (node (ref "PAD4") (pin "1") (pinfunction "P_1") (pintype "passive"))
      (node (ref "U2") (pin "1") (pinfunction "OUT1_1") (pintype "output"))
      (node (ref "U2") (pin "2") (pinfunction "OUT2_2") (pintype "output"))
      (node (ref "U2") (pin "6") (pinfunction "OUT3_6") (pintype "output"))
      (node (ref "U2") (pin "7") (pinfunction "OUT4_7") (pintype "output"))
    )
    (net (code "21") (name "MOTOR1_REV") (class "Default")
      (node (ref "PAD10") (pin "1") (pinfunction "P_1") (pintype "passive"))
      (node (ref "Q4") (pin "3") (pinfunction "D_3") (pintype "bidirectional"))
      (node (ref "R4") (pin "1") (pinfunction "1_1") (pintype "passive"))
    )
    (net (code "22") (name "MOTOR1_SENSE_AD") (class "Default")
      (node (ref "C3") (pin "1") (pinfunction "1_1") (pintype "passive"))
      (node (ref "D2") (pin "3") (pinfunction "C_3") (pintype "passive"))
      (node (ref "R7") (pin "2") (pinfunction "2_2") (pintype "passive"))
      (node (ref "U$1") (pin "84") (pinfunction "AIN3_84") (pintype "passive"))
      (node (ref "U2") (pin "5") (pinfunction "IS_5") (pintype "output"))
    )
    (net (code "23") (name "MOTOR1_TACH") (class "Default")
      (node (ref "PAD11") (pin "1") (pinfunction "P_1") (pintype "passive"))
      (node (ref "Q6") (pin "1") (pinfunction "G_1") (pintype "bidirectional"))
    )
    (net (code "24") (name "MOTOR1_TACH_FILT") (class "Default")
      (node (ref "Q6") (pin "3") (pinfunction "D_3") (pintype "bidirectional"))
      (node (ref "R6") (pin "1") (pinfunction "1_1") (pintype "passive"))
      (node (ref "U$1") (pin "16") (pinfunction "GPIO1_14_16") (pintype "passive"))
    )
    (net (code "25") (name "MOTOR1_TRIGGER") (class "Default")
      (node (ref "IC2") (pin "8") (pinfunction "VOUT_8") (pintype "output"))
      (node (ref "PAD8") (pin "1") (pinfunction "P_1") (pintype "passive"))
    )
    (net (code "26") (name "Net-(LED1-PadA)") (class "Default")
      (node (ref "LED1") (pin "A") (pinfunction "A_A") (pintype "passive"))
      (node (ref "R15") (pin "1") (pinfunction "1_1") (pintype "passive"))
    )
    (net (code "27") (name "Net-(LED2-PadA)") (class "Default")
      (node (ref "LED2") (pin "A") (pinfunction "A_A") (pintype "passive"))
      (node (ref "R12") (pin "1") (pinfunction "1_1") (pintype "passive"))
    )
    (net (code "28") (name "Net-(LED3-PadA)") (class "Default")
      (node (ref "LED3") (pin "A") (pinfunction "A_A") (pintype "passive"))
      (node (ref "R19") (pin "1") (pinfunction "1_1") (pintype "passive"))
    )
    (net (code "29") (name "Net-(LED4-PadA)") (class "Default")
      (node (ref "LED4") (pin "A") (pinfunction "A_A") (pintype "passive"))
      (node (ref "R20") (pin "1") (pinfunction "1_1") (pintype "passive"))
    )
    (net (code "30") (name "Net-(LED5-PadA)") (class "Default")
      (node (ref "LED5") (pin "A") (pinfunction "A_A") (pintype "passive"))
      (node (ref "R21") (pin "1") (pinfunction "1_1") (pintype "passive"))
    )
    (net (code "31") (name "Net-(LED6-PadA)") (class "Default")
      (node (ref "LED6") (pin "A") (pinfunction "A_A") (pintype "passive"))
      (node (ref "R22") (pin "1") (pinfunction "1_1") (pintype "passive"))
    )
    (net (code "32") (name "Net-(LED7-PadA)") (class "Default")
      (node (ref "LED7") (pin "A") (pinfunction "A_A") (pintype "passive"))
      (node (ref "R23") (pin "1") (pinfunction "1_1") (pintype "passive"))
    )
    (net (code "33") (name "Net-(Q7-D)") (class "Default")
      (node (ref "Q7") (pin "3") (pinfunction "D_3") (pintype "bidirectional"))
      (node (ref "U1") (pin "3") (pinfunction "IN_3") (pintype "input"))
    )
    (net (code "34") (name "Net-(Q8-D)") (class "Default")
      (node (ref "Q8") (pin "3") (pinfunction "D_3") (pintype "bidirectional"))
      (node (ref "U2") (pin "3") (pinfunction "IN_3") (pintype "input"))
    )
    (net (code "35") (name "SPI0_CS") (class "Default")
      (node (ref "IC1") (pin "2") (pinfunction "CS_2") (pintype "input"))
      (node (ref "U$1") (pin "63") (pinfunction "I2C1_SCL_63") (pintype "passive"))
    )
    (net (code "36") (name "SPI0_MOSI") (class "Default")
      (node (ref "IC1") (pin "4") (pinfunction "SDI_4") (pintype "input"))
      (node (ref "U$1") (pin "67") (pinfunction "UART2_TXD_67") (pintype "passive"))
    )
    (net (code "37") (name "SPI0_SCLK") (class "Default")
      (node (ref "IC1") (pin "3") (pinfunction "SCK_3") (pintype "input"))
      (node (ref "U$1") (pin "68") (pinfunction "UART2_RXD_68") (pintype "passive"))
    )
    (net (code "38") (name "SPI1_CS") (class "Default")
      (node (ref "IC2") (pin "2") (pinfunction "CS_2") (pintype "input"))
      (node (ref "U$1") (pin "74") (pinfunction "SPI1_CS0_74") (pintype "passive"))
    )
    (net (code "39") (name "SPI1_MOSI") (class "Default")
      (node (ref "IC2") (pin "4") (pinfunction "SDI_4") (pintype "input"))
      (node (ref "U$1") (pin "75") (pinfunction "SPI1_DO_75") (pintype "passive"))
    )
    (net (code "40") (name "SPI1_SCLK") (class "Default")
      (node (ref "IC2") (pin "3") (pinfunction "SCK_3") (pintype "input"))
      (node (ref "U$1") (pin "77") (pinfunction "SPI1_SCLK_77") (pintype "passive"))
    )
    (net (code "41") (name "SYS_5V") (class "Default")
      (node (ref "U$1") (pin "53") (pinfunction "SYS_5V_53") (pintype "power_in"))
    )
    (net (code "42") (name "VBATT") (class "Default")
      (node (ref "D7") (pin "A") (pinfunction "A_A") (pintype "passive"))
      (node (ref "PAD13") (pin "1") (pinfunction "P_1") (pintype "passive"))
    )
    (net (code "43") (name "VBATT_FILT") (class "Default")
      (node (ref "C7") (pin "1") (pinfunction "1_1") (pintype "passive"))
      (node (ref "D7") (pin "C") (pinfunction "C_C") (pintype "passive"))
      (node (ref "IC3") (pin "1") (pinfunction "VI_1") (pintype "input"))
      (node (ref "R24") (pin "2") (pinfunction "2_2") (pintype "passive"))
    )
    (net (code "44") (name "VBATT_SENSE_AD") (class "Default")
      (node (ref "C9") (pin "1") (pinfunction "1_1") (pintype "passive"))
      (node (ref "D5") (pin "3") (pinfunction "C_3") (pintype "passive"))
      (node (ref "R24") (pin "1") (pinfunction "1_1") (pintype "passive"))
      (node (ref "R25") (pin "1") (pinfunction "1_1") (pintype "passive"))
      (node (ref "U$1") (pin "79") (pinfunction "AIN4_79") (pintype "passive"))
    )
    (net (code "45") (name "VBB") (class "Default")
      (node (ref "U2") (pin "4") (pinfunction "VBB_4") (pintype "power_in"))
    )
    (net (code "46") (name "VCC") (class "Default")
      (node (ref "PAD1") (pin "1") (pinfunction "P_1") (pintype "passive"))
      (node (ref "R13") (pin "2") (pinfunction "2_2") (pintype "passive"))
      (node (ref "U1") (pin "8") (pinfunction "VBB_8") (pintype "power_in"))
    )
    (net (code "47") (name "VCC_SENSE_AD") (class "Default")
      (node (ref "C5") (pin "1") (pinfunction "1_1") (pintype "passive"))
      (node (ref "D3") (pin "3") (pinfunction "C_3") (pintype "passive"))
      (node (ref "R13") (pin "1") (pinfunction "1_1") (pintype "passive"))
      (node (ref "R16") (pin "1") (pinfunction "1_1") (pintype "passive"))
      (node (ref "U$1") (pin "83") (pinfunction "AIN2_83") (pintype "passive"))
    )
    (net (code "48") (name "VDD") (class "Default")
      (node (ref "PAD3") (pin "1") (pinfunction "P_1") (pintype "passive"))
      (node (ref "R17") (pin "2") (pinfunction "2_2") (pintype "passive"))
      (node (ref "U2") (pin "8") (pinfunction "VBB_8") (pintype "power_in"))
    )
    (net (code "49") (name "VDD_SENSE_AD") (class "Default")
      (node (ref "C6") (pin "1") (pinfunction "1_1") (pintype "passive"))
      (node (ref "D4") (pin "3") (pinfunction "C_3") (pintype "passive"))
      (node (ref "R17") (pin "1") (pinfunction "1_1") (pintype "passive"))
      (node (ref "R18") (pin "1") (pinfunction "1_1") (pintype "passive"))
      (node (ref "U$1") (pin "85") (pinfunction "AIN0_85") (pintype "power_in"))
    )
    (net (code "50") (name "unconnected-(U$1-AIN5-Pad82)") (class "Default")
      (node (ref "U$1") (pin "82") (pinfunction "AIN5_82") (pintype "passive"))
    )
    (net (code "51") (name "unconnected-(U$1-AIN6-Pad81)") (class "Default")
      (node (ref "U$1") (pin "81") (pinfunction "AIN6_81") (pintype "passive"))
    )
    (net (code "52") (name "unconnected-(U$1-EHRPWM2A-Pad19)") (class "Default")
      (node (ref "U$1") (pin "19") (pinfunction "EHRPWM2A_19") (pintype "passive"))
    )
    (net (code "53") (name "unconnected-(U$1-EHRPWM2B-Pad13)") (class "Default")
      (node (ref "U$1") (pin "13") (pinfunction "EHRPWM2B_13") (pintype "passive"))
    )
    (net (code "54") (name "unconnected-(U$1-GNDA_ADC-Pad80)") (class "Default")
      (node (ref "U$1") (pin "80") (pinfunction "GNDA_ADC_80") (pintype "passive"))
    )
    (net (code "55") (name "unconnected-(U$1-GPIO0_26-Pad14)") (class "Default")
      (node (ref "U$1") (pin "14") (pinfunction "GPIO0_26_14") (pintype "passive"))
    )
    (net (code "56") (name "unconnected-(U$1-GPIO0_27-Pad17)") (class "Default")
      (node (ref "U$1") (pin "17") (pinfunction "GPIO0_27_17") (pintype "passive"))
    )
    (net (code "57") (name "unconnected-(U$1-GPIO1_0-Pad25)") (class "Default")
      (node (ref "U$1") (pin "25") (pinfunction "GPIO1_0_25") (pintype "passive"))
    )
    (net (code "58") (name "unconnected-(U$1-GPIO1_1-Pad24)") (class "Default")
      (node (ref "U$1") (pin "24") (pinfunction "GPIO1_1_24") (pintype "passive"))
    )
    (net (code "59") (name "unconnected-(U$1-GPIO1_2-Pad5)") (class "Default")
      (node (ref "U$1") (pin "5") (pinfunction "GPIO1_2_5") (pintype "passive"))
    )
    (net (code "60") (name "unconnected-(U$1-GPIO1_3-Pad6)") (class "Default")
      (node (ref "U$1") (pin "6") (pinfunction "GPIO1_3_6") (pintype "passive"))
    )
    (net (code "61") (name "unconnected-(U$1-GPIO1_4-Pad23)") (class "Default")
      (node (ref "U$1") (pin "23") (pinfunction "GPIO1_4_23") (pintype "passive"))
    )
    (net (code "62") (name "unconnected-(U$1-GPIO1_5-Pad22)") (class "Default")
      (node (ref "U$1") (pin "22") (pinfunction "GPIO1_5_22") (pintype "passive"))
    )
    (net (code "63") (name "unconnected-(U$1-GPIO1_6-Pad3)") (class "Default")
      (node (ref "U$1") (pin "3") (pinfunction "GPIO1_6_3") (pintype "passive"))
    )
    (net (code "64") (name "unconnected-(U$1-GPIO1_7-Pad4)") (class "Default")
      (node (ref "U$1") (pin "4") (pinfunction "GPIO1_7_4") (pintype "passive"))
    )
    (net (code "65") (name "unconnected-(U$1-GPIO1_12-Pad12)") (class "Default")
      (node (ref "U$1") (pin "12") (pinfunction "GPIO1_12_12") (pintype "passive"))
    )
    (net (code "66") (name "unconnected-(U$1-GPIO1_13-Pad11)") (class "Default")
      (node (ref "U$1") (pin "11") (pinfunction "GPIO1_13_11") (pintype "passive"))
    )
    (net (code "67") (name "unconnected-(U$1-GPIO1_17-Pad69)") (class "Default")
      (node (ref "U$1") (pin "69") (pinfunction "GPIO1_17_69") (pintype "passive"))
    )
    (net (code "68") (name "unconnected-(U$1-GPIO1_29-Pad26)") (class "Default")
      (node (ref "U$1") (pin "26") (pinfunction "GPIO1_29_26") (pintype "passive"))
    )
    (net (code "69") (name "unconnected-(U$1-GPIO1_30-Pad21)") (class "Default")
      (node (ref "U$1") (pin "21") (pinfunction "GPIO1_30_21") (pintype "passive"))
    )
    (net (code "70") (name "unconnected-(U$1-GPIO1_31-Pad20)") (class "Default")
      (node (ref "U$1") (pin "20") (pinfunction "GPIO1_31_20") (pintype "passive"))
    )
    (net (code "71") (name "unconnected-(U$1-GPIO2_1-Pad18)") (class "Default")
      (node (ref "U$1") (pin "18") (pinfunction "GPIO2_1_18") (pintype "passive"))
    )
    (net (code "72") (name "unconnected-(U$1-GPIO2_6-Pad45)") (class "Default")
      (node (ref "U$1") (pin "45") (pinfunction "GPIO2_6_45") (pintype "passive"))
    )
    (net (code "73") (name "unconnected-(U$1-GPIO2_7-Pad46)") (class "Default")
      (node (ref "U$1") (pin "46") (pinfunction "GPIO2_7_46") (pintype "passive"))
    )
    (net (code "74") (name "unconnected-(U$1-GPIO2_8-Pad43)") (class "Default")
      (node (ref "U$1") (pin "43") (pinfunction "GPIO2_8_43") (pintype "passive"))
    )
    (net (code "75") (name "unconnected-(U$1-GPIO2_9-Pad44)") (class "Default")
      (node (ref "U$1") (pin "44") (pinfunction "GPIO2_9_44") (pintype "passive"))
    )
    (net (code "76") (name "unconnected-(U$1-GPIO2_10-Pad41)") (class "Default")
      (node (ref "U$1") (pin "41") (pinfunction "GPIO2_10_41") (pintype "passive"))
    )
    (net (code "77") (name "unconnected-(U$1-GPIO2_11-Pad42)") (class "Default")
      (node (ref "U$1") (pin "42") (pinfunction "GPIO2_11_42") (pintype "passive"))
    )
    (net (code "78") (name "unconnected-(U$1-GPIO2_12-Pad39)") (class "Default")
      (node (ref "U$1") (pin "39") (pinfunction "GPIO2_12_39") (pintype "passive"))
    )
    (net (code "79") (name "unconnected-(U$1-GPIO2_13-Pad40)") (class "Default")
      (node (ref "U$1") (pin "40") (pinfunction "GPIO2_13_40") (pintype "passive"))
    )
    (net (code "80") (name "unconnected-(U$1-GPIO2_22-Pad27)") (class "Default")
      (node (ref "U$1") (pin "27") (pinfunction "GPIO2_22_27") (pintype "passive"))
    )
    (net (code "81") (name "unconnected-(U$1-GPIO2_23-Pad29)") (class "Default")
      (node (ref "U$1") (pin "29") (pinfunction "GPIO2_23_29") (pintype "passive"))
    )
    (net (code "82") (name "unconnected-(U$1-GPIO2_24-Pad28)") (class "Default")
      (node (ref "U$1") (pin "28") (pinfunction "GPIO2_24_28") (pintype "passive"))
    )
    (net (code "83") (name "unconnected-(U$1-GPIO2_25-Pad30)") (class "Default")
      (node (ref "U$1") (pin "30") (pinfunction "GPIO2_25_30") (pintype "passive"))
    )
    (net (code "84") (name "unconnected-(U$1-GPIO3_19-Pad73)") (class "Default")
      (node (ref "U$1") (pin "73") (pinfunction "GPIO3_19_73") (pintype "passive"))
    )
    (net (code "85") (name "unconnected-(U$1-GPIO3_21-Pad71)") (class "Default")
      (node (ref "U$1") (pin "71") (pinfunction "GPIO3_21_71") (pintype "passive"))
    )
    (net (code "86") (name "unconnected-(U$1-I2C1_SDA-Pad64)") (class "Default")
      (node (ref "U$1") (pin "64") (pinfunction "I2C1_SDA_64") (pintype "passive"))
    )
    (net (code "87") (name "unconnected-(U$1-I2C2_SCL-Pad65)") (class "Default")
      (node (ref "U$1") (pin "65") (pinfunction "I2C2_SCL_65") (pintype "passive"))
    )
    (net (code "88") (name "unconnected-(U$1-I2C2_SDA-Pad66)") (class "Default")
      (node (ref "U$1") (pin "66") (pinfunction "I2C2_SDA_66") (pintype "passive"))
    )
    (net (code "89") (name "unconnected-(U$1-PWR_BUT-Pad55)") (class "Default")
      (node (ref "U$1") (pin "55") (pinfunction "PWR_BUT_55") (pintype "passive"))
    )
    (net (code "90") (name "unconnected-(U$1-SPI1_DI-Pad76)") (class "Default")
      (node (ref "U$1") (pin "76") (pinfunction "SPI1_DI_76") (pintype "passive"))
    )
    (net (code "91") (name "unconnected-(U$1-SYS_5V-Pad54)") (class "Default")
      (node (ref "U$1") (pin "54") (pinfunction "SYS_5V_54") (pintype "passive"))
    )
    (net (code "92") (name "unconnected-(U$1-SYS_RESETN-Pad56)") (class "Default")
      (node (ref "U$1") (pin "56") (pinfunction "SYS_RESETN_56") (pintype "passive"))
    )
    (net (code "93") (name "unconnected-(U$1-TIMER4-Pad7)") (class "Default")
      (node (ref "U$1") (pin "7") (pinfunction "TIMER4_7") (pintype "passive"))
    )
    (net (code "94") (name "unconnected-(U$1-TIMER5-Pad9)") (class "Default")
      (node (ref "U$1") (pin "9") (pinfunction "TIMER5_9") (pintype "passive"))
    )
    (net (code "95") (name "unconnected-(U$1-TIMER6-Pad10)") (class "Default")
      (node (ref "U$1") (pin "10") (pinfunction "TIMER6_10") (pintype "passive"))
    )
    (net (code "96") (name "unconnected-(U$1-TIMER7-Pad8)") (class "Default")
      (node (ref "U$1") (pin "8") (pinfunction "TIMER7_8") (pintype "passive"))
    )
    (net (code "97") (name "unconnected-(U$1-UART1_RXD-Pad72)") (class "Default")
      (node (ref "U$1") (pin "72") (pinfunction "UART1_RXD_72") (pintype "passive"))
    )
    (net (code "98") (name "unconnected-(U$1-UART1_TXD-Pad70)") (class "Default")
      (node (ref "U$1") (pin "70") (pinfunction "UART1_TXD_70") (pintype "passive"))
    )
    (net (code "99") (name "unconnected-(U$1-UART3_CTSN-Pad36)") (class "Default")
      (node (ref "U$1") (pin "36") (pinfunction "UART3_CTSN_36") (pintype "passive"))
    )
    (net (code "100") (name "unconnected-(U$1-UART3_RTSN-Pad34)") (class "Default")
      (node (ref "U$1") (pin "34") (pinfunction "UART3_RTSN_34") (pintype "passive"))
    )
    (net (code "101") (name "unconnected-(U$1-UART4_CTSN-Pad35)") (class "Default")
      (node (ref "U$1") (pin "35") (pinfunction "UART4_CTSN_35") (pintype "passive"))
    )
    (net (code "102") (name "unconnected-(U$1-UART4_RTSN-Pad33)") (class "Default")
      (node (ref "U$1") (pin "33") (pinfunction "UART4_RTSN_33") (pintype "passive"))
    )
    (net (code "103") (name "unconnected-(U$1-UART4_RXD-Pad57)") (class "Default")
      (node (ref "U$1") (pin "57") (pinfunction "UART4_RXD_57") (pintype "passive"))
    )
    (net (code "104") (name "unconnected-(U$1-UART4_TXD-Pad59)") (class "Default")
      (node (ref "U$1") (pin "59") (pinfunction "UART4_TXD_59") (pintype "passive"))
    )
    (net (code "105") (name "unconnected-(U$1-UART5_CTSN-Pad31)") (class "Default")
      (node (ref "U$1") (pin "31") (pinfunction "UART5_CTSN_31") (pintype "passive"))
    )
    (net (code "106") (name "unconnected-(U$1-UART5_RTSN-Pad32)") (class "Default")
      (node (ref "U$1") (pin "32") (pinfunction "UART5_RTSN_32") (pintype "passive"))
    )
    (net (code "107") (name "unconnected-(U$1-UART5_RXD-Pad38)") (class "Default")
      (node (ref "U$1") (pin "38") (pinfunction "UART5_RXD_38") (pintype "passive"))
    )
    (net (code "108") (name "unconnected-(U$1-UART5_TXD-Pad37)") (class "Default")
      (node (ref "U$1") (pin "37") (pinfunction "UART5_TXD_37") (pintype "passive"))
    )
    (net (code "109") (name "unconnected-(U$1-VDD_ADC-Pad78)") (class "Default")
      (node (ref "U$1") (pin "78") (pinfunction "VDD_ADC_78") (pintype "passive"))
    )
    (net (code "110") (name "unconnected-(U1-VBB-Pad4)") (class "Default")
      (node (ref "U1") (pin "4") (pinfunction "VBB_4") (pintype "power_in"))
    )
  )
)
